# MRCS-Relay-Latch.net
KiCad netlist of a schematic drawn in EAGLE
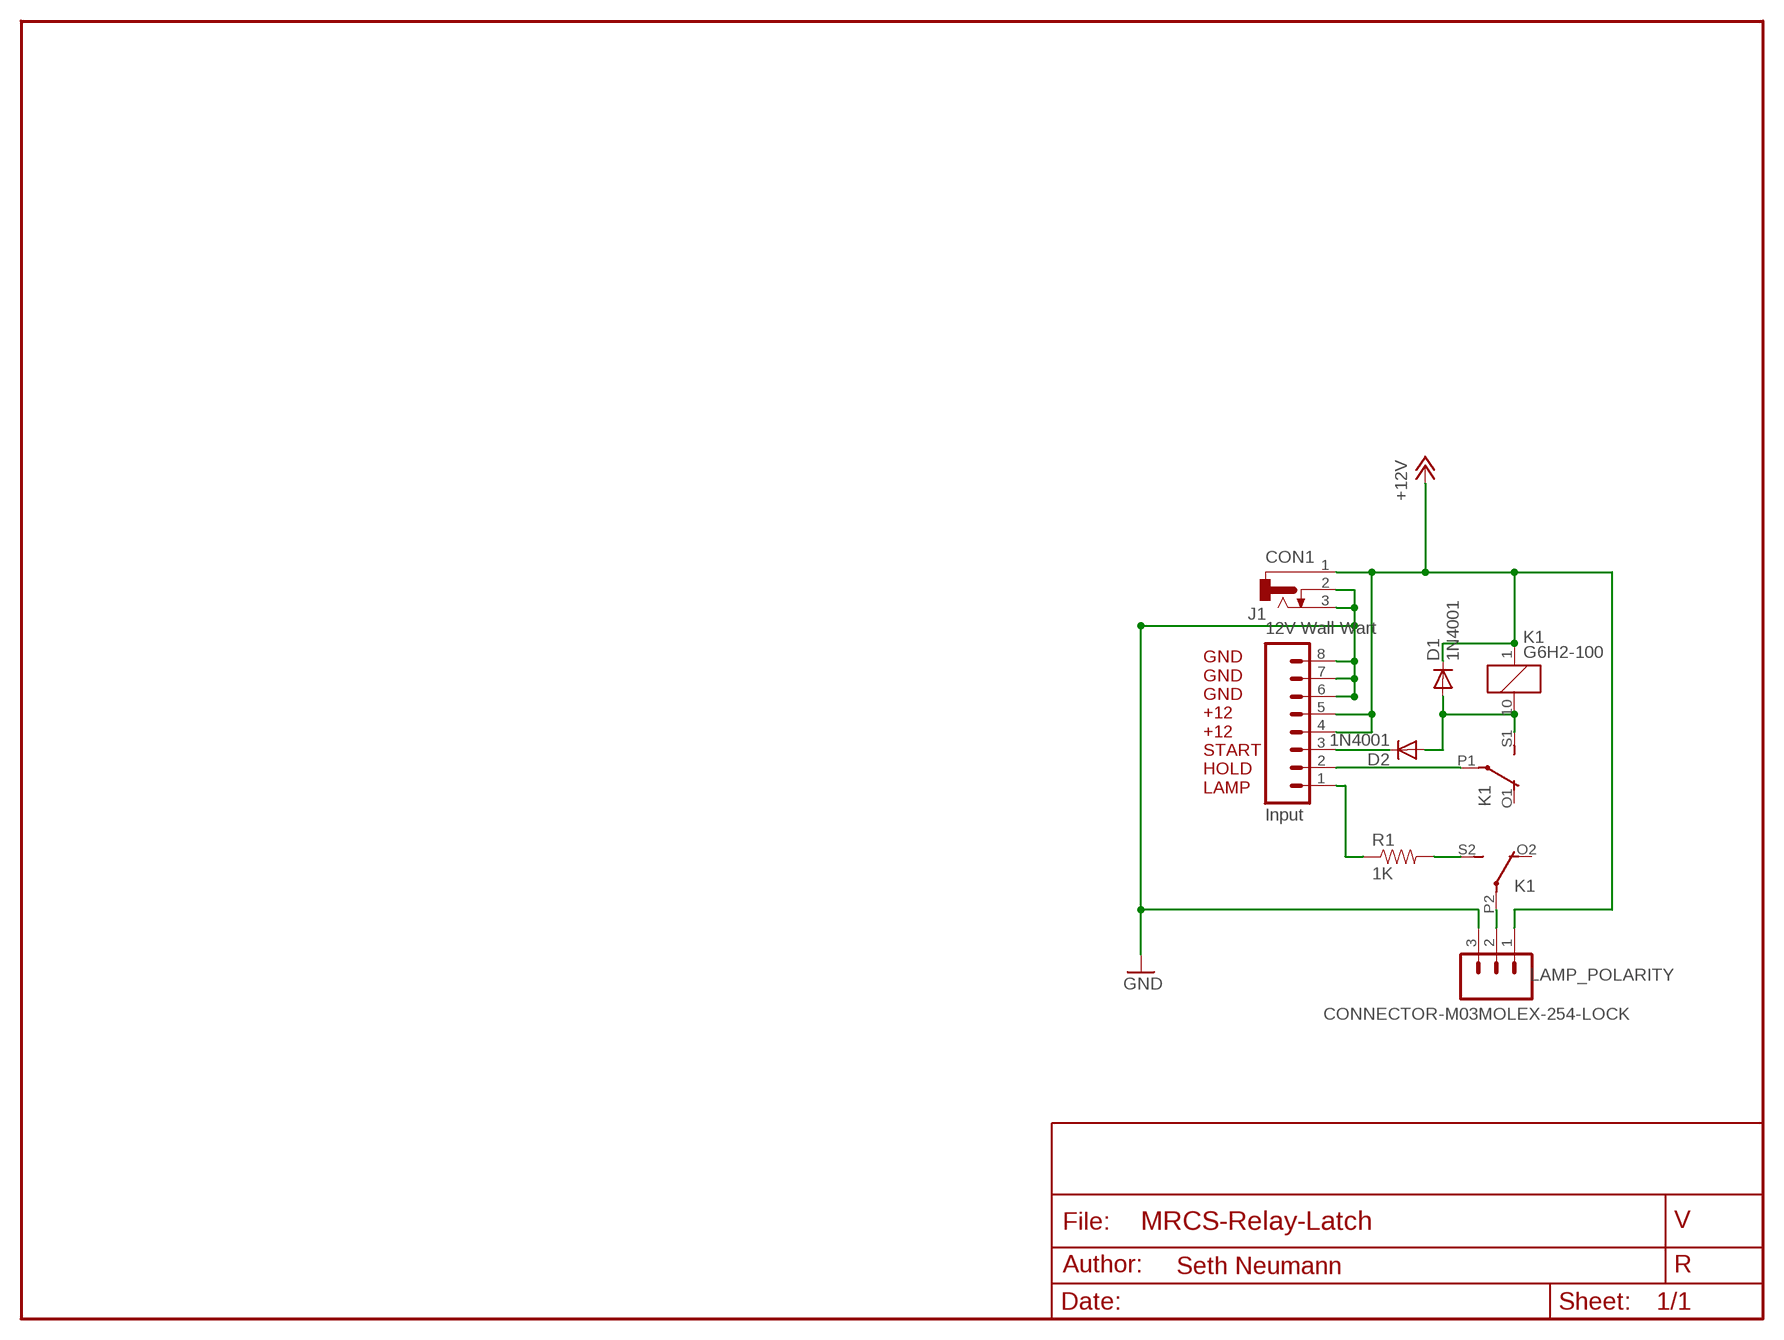
[diagram p0: schematic, sheet 1]

(export (version "E")
  (design (tool "Eeschema 10.0.6"))
  (components
    (comp (ref "CON1")
      (value "12V Wall Wart")
      (footprint "eagle-import:DCJ0202")
      (libsource (lib "eagle-import") (part "CONNECTOR-DC-POWER-RA"))
    )
    (comp (ref "D1")
      (value "1N4001")
      (footprint "eagle-import:DIODE-1N4001")
      (libsource (lib "eagle-import") (part "DIODEPTH"))
    )
    (comp (ref "D2")
      (value "1N4001")
      (footprint "eagle-import:DIODE-1N4001")
      (libsource (lib "eagle-import") (part "DIODEPTH"))
    )
    (comp (ref "J1")
      (value "Input")
      (footprint "eagle-import:1X08_FEMALE_LOCK")
      (libsource (lib "eagle-import") (part "CONNECTOR-M08FEMALE_LOCK"))
    )
    (comp (ref "K1")
      (value "G6H2-100")
      (footprint "eagle-import:G6H2-100")
      (libsource (lib "eagle-import") (part "G6H2-100"))
    )
    (comp (ref "LAMP_POLARITY")
      (value "CONNECTOR-M03MOLEX-254-LOCK")
      (footprint "eagle-import:MOLEX-1X3_LOCK")
      (libsource (lib "eagle-import") (part "CONNECTOR-M03MOLEX-254-LOCK"))
    )
    (comp (ref "R1")
      (value "1K")
      (footprint "eagle-import:AXIAL-0.4-RES")
      (libsource (lib "eagle-import") (part "RPTH04"))
    )
  )
  (nets
    (net (code "1") (name "+12V") (class "Default")
      (node (ref "CON1") (pin "1") (pinfunction "1_1") (pintype "passive"))
      (node (ref "D1") (pin "C") (pinfunction "C_C") (pintype "passive"))
      (node (ref "J1") (pin "4") (pinfunction "4_4") (pintype "passive"))
      (node (ref "J1") (pin "5") (pinfunction "5_5") (pintype "passive"))
      (node (ref "K1") (pin "1") (pinfunction "1_1") (pintype "passive"))
      (node (ref "LAMP_POLARITY") (pin "1") (pinfunction "1_1") (pintype "passive"))
    )
    (net (code "2") (name "GND") (class "Default")
      (node (ref "CON1") (pin "2") (pinfunction "2_2") (pintype "passive"))
      (node (ref "CON1") (pin "3") (pinfunction "3_3") (pintype "passive"))
      (node (ref "J1") (pin "6") (pinfunction "6_6") (pintype "passive"))
      (node (ref "J1") (pin "7") (pinfunction "7_7") (pintype "passive"))
      (node (ref "J1") (pin "8") (pinfunction "8_8") (pintype "passive"))
      (node (ref "LAMP_POLARITY") (pin "3") (pinfunction "3_3") (pintype "passive"))
    )
    (net (code "3") (name "Net-(D2-PadC)") (class "Default")
      (node (ref "D2") (pin "C") (pinfunction "C_C") (pintype "passive"))
      (node (ref "J1") (pin "3") (pinfunction "3_3") (pintype "passive"))
    )
    (net (code "4") (name "Net-(K1A-2)") (class "Default")
      (node (ref "D1") (pin "A") (pinfunction "A_A") (pintype "passive"))
      (node (ref "D2") (pin "A") (pinfunction "A_A") (pintype "passive"))
      (node (ref "K1") (pin "10") (pinfunction "2_10") (pintype "passive"))
      (node (ref "K1") (pin "S1") (pinfunction "S_S1") (pintype "passive"))
    )
    (net (code "5") (name "Net-(K1B-P)") (class "Default")
      (node (ref "J1") (pin "2") (pinfunction "2_2") (pintype "passive"))
      (node (ref "K1") (pin "P1") (pinfunction "P_P1") (pintype "passive"))
    )
    (net (code "6") (name "Net-(K1C-P)") (class "Default")
      (node (ref "K1") (pin "P2") (pinfunction "P_P2") (pintype "passive"))
      (node (ref "LAMP_POLARITY") (pin "2") (pinfunction "2_2") (pintype "passive"))
    )
    (net (code "7") (name "Net-(K1C-S)") (class "Default")
      (node (ref "K1") (pin "S2") (pinfunction "S_S2") (pintype "passive"))
      (node (ref "R1") (pin "P$2") (pinfunction "2_P$2") (pintype "passive"))
    )
    (net (code "8") (name "Net-(R1-1)") (class "Default")
      (node (ref "J1") (pin "1") (pinfunction "1_1") (pintype "passive"))
      (node (ref "R1") (pin "P$1") (pinfunction "1_P$1") (pintype "passive"))
    )
    (net (code "9") (name "unconnected-(K1B-O-PadO1)") (class "Default")
      (node (ref "K1") (pin "O1") (pinfunction "O_O1") (pintype "passive"))
    )
    (net (code "10") (name "unconnected-(K1C-O-PadO2)") (class "Default")
      (node (ref "K1") (pin "O2") (pinfunction "O_O2") (pintype "passive"))
    )
  )
)
